# SCH_TB6612_24_2025-07-27.net
KiCad netlist of a schematic drawn in EasyEDA
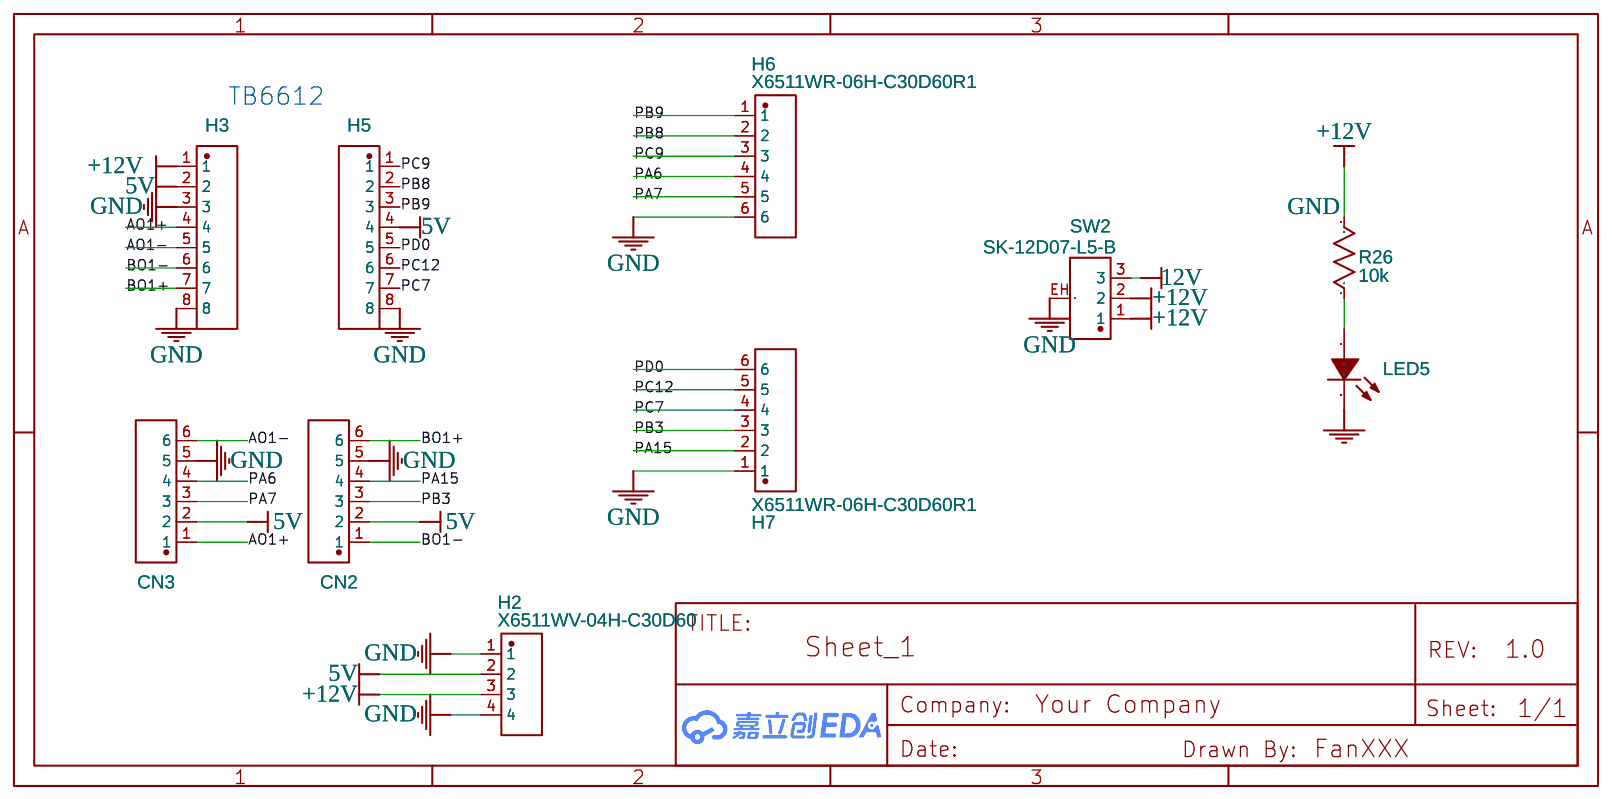
[diagram p0: schematic sheet]

(export (version "E")
  (design (tool "Eeschema 10.0.6"))
  (components
    (comp (ref "CN2")
      (value "X8821WR-06S-N0SN")
      (fields (field (name "Manufacturer") "XKB Connectivity(中国星坤)"))
      (libsource (lib "") (part "X8821WR-06S-N0SN"))
    )
    (comp (ref "CN3")
      (value "X8821WR-06S-N0SN")
      (fields (field (name "Manufacturer") "XKB Connectivity(中国星坤)"))
      (libsource (lib "") (part "X8821WR-06S-N0SN"))
    )
    (comp (ref "H2")
      (value "X6511WV-04H-C30D60")
      (fields (field (name "Manufacturer") "XKB Connectivity(中国星坤)"))
      (libsource (lib "") (part "X6511WV-04H-C30D60"))
    )
    (comp (ref "H3")
      (value "X6511FV-08-C85D32")
      (fields (field (name "Manufacturer") "XKB Connectivity(中国星坤)"))
      (libsource (lib "") (part "X6511FV-08-C85D32_1"))
    )
    (comp (ref "H5")
      (value "X6511FV-08-C85D32")
      (fields (field (name "Manufacturer") "XKB Connectivity(中国星坤)"))
      (libsource (lib "") (part "X6511FV-08-C85D32"))
    )
    (comp (ref "H6")
      (value "X6511WR-06H-C30D60R1")
      (fields (field (name "Manufacturer") "XKB Connectivity(中国星坤)"))
      (libsource (lib "") (part "X6511WR-06H-C30D60R1"))
    )
    (comp (ref "H7")
      (value "X6511WR-06H-C30D60R1")
      (fields (field (name "Manufacturer") "XKB Connectivity(中国星坤)"))
      (libsource (lib "") (part "X6511WR-06H-C30D60R1_1"))
    )
    (comp (ref "LED5")
      (value "FC-A2012WD-457H5")
      (fields (field (name "Manufacturer") "NATIONSTAR"))
      (libsource (lib "") (part "FC-A2012WD-457H5"))
    )
    (comp (ref "R26") (value "10k") (libsource (lib "") (part "R_0603_US")))
    (comp (ref "SW2")
      (value "SK-12D07-L5-B")
      (fields (field (name "Manufacturer") "XKB Enterprise"))
      (libsource (lib "") (part "SK-12D07-L5-B"))
    )
  )
  (nets
    (net (code "1") (name "+12V") (class "Default")
      (node (ref "H2") (pin "3") (pinfunction "3_3") (pintype "unspecified"))
      (node (ref "H3") (pin "1") (pinfunction "1_1") (pintype "unspecified"))
      (node (ref "R26") (pin "2") (pinfunction "2_2") (pintype "unspecified"))
      (node (ref "SW2") (pin "1") (pinfunction "1_1") (pintype "unspecified"))
      (node (ref "SW2") (pin "2") (pinfunction "2_2") (pintype "unspecified"))
    )
    (net (code "2") (name "/AO1+") (class "Default")
      (node (ref "CN3") (pin "1") (pinfunction "1_1") (pintype "unspecified"))
      (node (ref "H3") (pin "4") (pinfunction "4_4") (pintype "unspecified"))
    )
    (net (code "3") (name "/AO1-") (class "Default")
      (node (ref "CN3") (pin "6") (pinfunction "6_6") (pintype "unspecified"))
      (node (ref "H3") (pin "5") (pinfunction "5_5") (pintype "unspecified"))
    )
    (net (code "4") (name "/BO1+") (class "Default")
      (node (ref "CN2") (pin "6") (pinfunction "6_6") (pintype "unspecified"))
      (node (ref "H3") (pin "7") (pinfunction "7_7") (pintype "unspecified"))
    )
    (net (code "5") (name "/BO1-") (class "Default")
      (node (ref "CN2") (pin "1") (pinfunction "1_1") (pintype "unspecified"))
      (node (ref "H3") (pin "6") (pinfunction "6_6") (pintype "unspecified"))
    )
    (net (code "6") (name "/PA6") (class "Default")
      (node (ref "CN3") (pin "4") (pinfunction "4_4") (pintype "unspecified"))
      (node (ref "H6") (pin "4") (pinfunction "4_4") (pintype "unspecified"))
    )
    (net (code "7") (name "/PA7") (class "Default")
      (node (ref "CN3") (pin "3") (pinfunction "3_3") (pintype "unspecified"))
      (node (ref "H6") (pin "5") (pinfunction "5_5") (pintype "unspecified"))
    )
    (net (code "8") (name "/PA15") (class "Default")
      (node (ref "CN2") (pin "4") (pinfunction "4_4") (pintype "unspecified"))
      (node (ref "H7") (pin "2") (pinfunction "2_2") (pintype "unspecified"))
    )
    (net (code "9") (name "/PB3") (class "Default")
      (node (ref "CN2") (pin "3") (pinfunction "3_3") (pintype "unspecified"))
      (node (ref "H7") (pin "3") (pinfunction "3_3") (pintype "unspecified"))
    )
    (net (code "10") (name "/PB8") (class "Default")
      (node (ref "H5") (pin "2") (pinfunction "2_2") (pintype "unspecified"))
      (node (ref "H6") (pin "2") (pinfunction "2_2") (pintype "unspecified"))
    )
    (net (code "11") (name "/PB9") (class "Default")
      (node (ref "H5") (pin "3") (pinfunction "3_3") (pintype "unspecified"))
      (node (ref "H6") (pin "1") (pinfunction "1_1") (pintype "unspecified"))
    )
    (net (code "12") (name "/PC7") (class "Default")
      (node (ref "H5") (pin "7") (pinfunction "7_7") (pintype "unspecified"))
      (node (ref "H7") (pin "4") (pinfunction "4_4") (pintype "unspecified"))
    )
    (net (code "13") (name "/PC9") (class "Default")
      (node (ref "H5") (pin "1") (pinfunction "1_1") (pintype "unspecified"))
      (node (ref "H6") (pin "3") (pinfunction "3_3") (pintype "unspecified"))
    )
    (net (code "14") (name "/PC12") (class "Default")
      (node (ref "H5") (pin "6") (pinfunction "6_6") (pintype "unspecified"))
      (node (ref "H7") (pin "5") (pinfunction "5_5") (pintype "unspecified"))
    )
    (net (code "15") (name "/PD0") (class "Default")
      (node (ref "H5") (pin "5") (pinfunction "5_5") (pintype "unspecified"))
      (node (ref "H7") (pin "6") (pinfunction "6_6") (pintype "unspecified"))
    )
    (net (code "16") (name "5V") (class "Default")
      (node (ref "CN2") (pin "2") (pinfunction "2_2") (pintype "unspecified"))
      (node (ref "CN3") (pin "2") (pinfunction "2_2") (pintype "unspecified"))
      (node (ref "H2") (pin "2") (pinfunction "2_2") (pintype "unspecified"))
      (node (ref "H3") (pin "2") (pinfunction "2_2") (pintype "unspecified"))
      (node (ref "H5") (pin "4") (pinfunction "4_4") (pintype "unspecified"))
    )
    (net (code "17") (name "12V") (class "Default")
      (node (ref "SW2") (pin "3") (pinfunction "3_3") (pintype "unspecified"))
    )
    (net (code "18") (name "GND") (class "Default")
      (node (ref "CN2") (pin "5") (pinfunction "5_5") (pintype "unspecified"))
      (node (ref "CN3") (pin "5") (pinfunction "5_5") (pintype "unspecified"))
      (node (ref "H2") (pin "1") (pinfunction "1_1") (pintype "unspecified"))
      (node (ref "H2") (pin "4") (pinfunction "4_4") (pintype "unspecified"))
      (node (ref "H3") (pin "3") (pinfunction "3_3") (pintype "unspecified"))
      (node (ref "H3") (pin "8") (pinfunction "8_8") (pintype "unspecified"))
      (node (ref "H5") (pin "8") (pinfunction "8_8") (pintype "unspecified"))
      (node (ref "H6") (pin "6") (pinfunction "6_6") (pintype "unspecified"))
      (node (ref "H7") (pin "1") (pinfunction "1_1") (pintype "unspecified"))
      (node (ref "LED5") (pin "2") (pinfunction "K_2") (pintype "unspecified"))
      (node (ref "SW2") (pin "EH") (pinfunction "EH_EH") (pintype "unspecified"))
    )
    (net (code "19") (name "Net-(LED5-A)") (class "Default")
      (node (ref "LED5") (pin "1") (pinfunction "A_1") (pintype "unspecified"))
      (node (ref "R26") (pin "1") (pinfunction "1_1") (pintype "unspecified"))
    )
  )
)
